# C8T6.net
KiCad netlist of a schematic drawn in Altium Designer
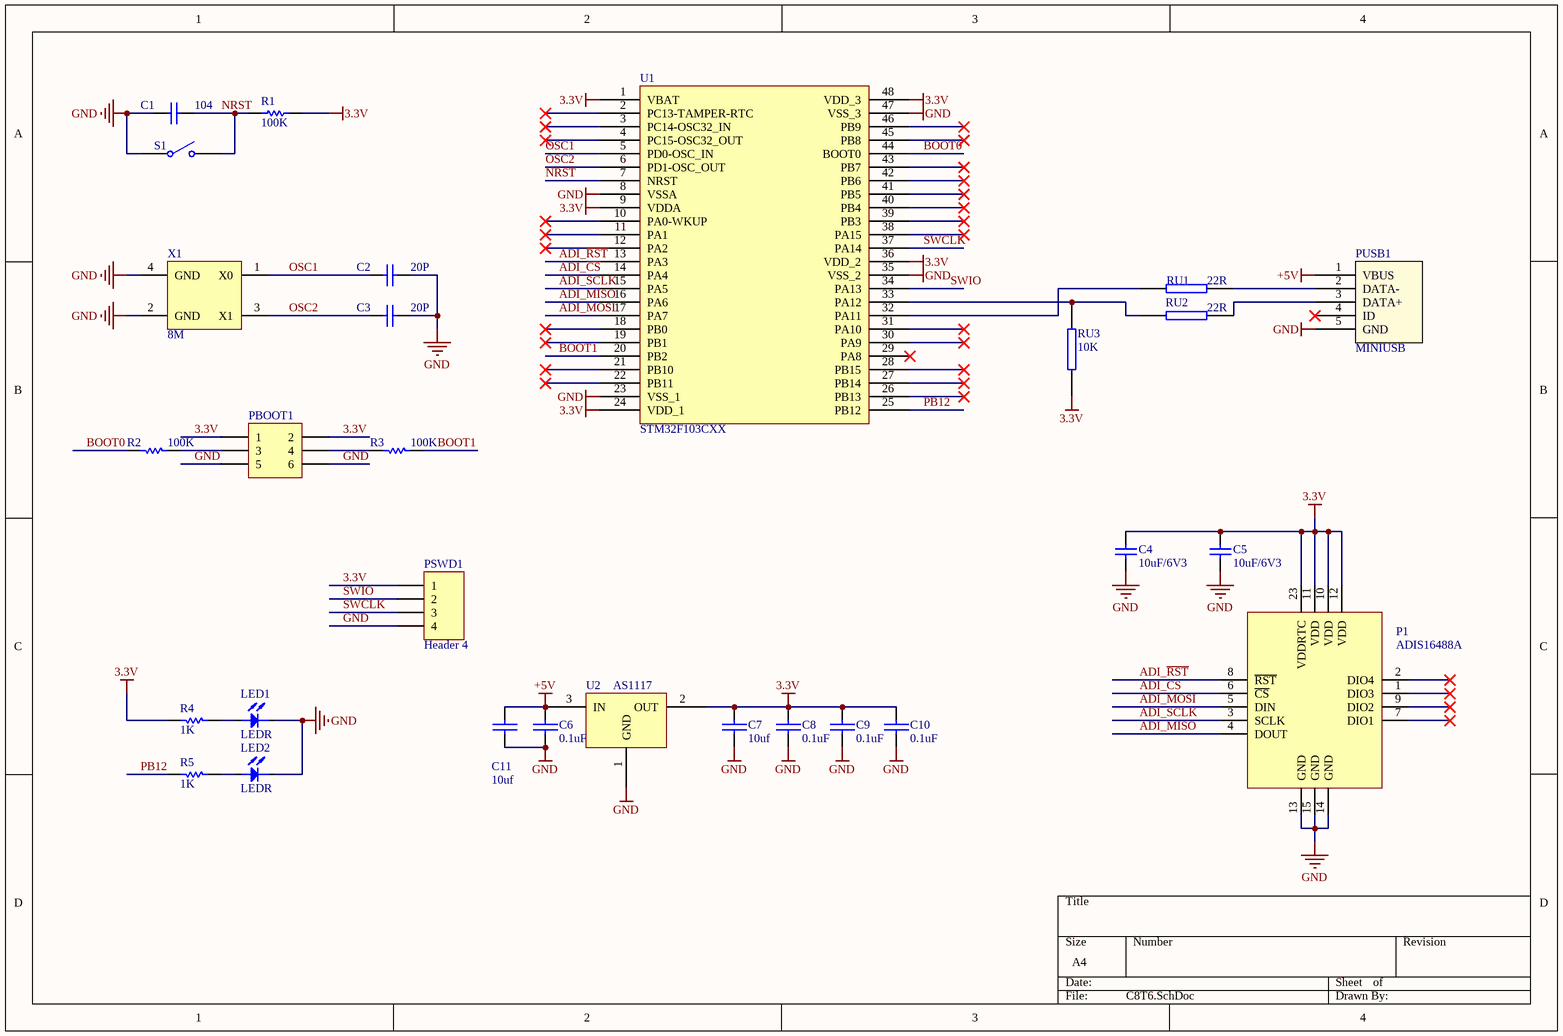
[diagram p0: C8T6.SchDoc]

(export (version "E")
  (design (tool "Eeschema 10.0.6"))
  (components
    (comp (ref "C1")
      (value "104")
      (footprint "0805_C")
      (description "Ceramic Capacitor")
      (fields (field (name "PUBLISHER") "Altium Limited"))
      (libsource (lib "My Devices") (part "Cap Cer"))
    )
    (comp (ref "C2")
      (value "20P")
      (footprint "0805_C")
      (description "Ceramic Capacitor")
      (fields (field (name "PUBLISHER") "Altium Limited"))
      (libsource (lib "My Devices") (part "Cap Cer"))
    )
    (comp (ref "C3")
      (value "20P")
      (footprint "0805_C")
      (description "Ceramic Capacitor")
      (fields (field (name "PUBLISHER") "Altium Limited"))
      (libsource (lib "My Devices") (part "Cap Cer"))
    )
    (comp (ref "C4")
      (value "10uF/6V3")
      (footprint "0805_C")
      (description "Ceramic Capacitor")
      (fields (field (name "PUBLISHER") "Altium Limited"))
      (libsource (lib "My Devices") (part "Cap Cer"))
    )
    (comp (ref "C5")
      (value "10uF/6V3")
      (footprint "0805_C")
      (description "Ceramic Capacitor")
      (fields (field (name "PUBLISHER") "Altium Limited"))
      (libsource (lib "My Devices") (part "Cap Cer"))
    )
    (comp (ref "C6")
      (value "0.1uF")
      (footprint "0805_C")
      (description "Capacitor")
      (libsource (lib "Miscellaneous Devices") (part "CAP"))
    )
    (comp (ref "C7")
      (value "10uf")
      (footprint "0805_C")
      (description "Capacitor")
      (libsource (lib "Miscellaneous Devices") (part "CAP"))
    )
    (comp (ref "C8")
      (value "0.1uF")
      (footprint "0805_C")
      (description "Capacitor")
      (libsource (lib "Miscellaneous Devices") (part "CAP"))
    )
    (comp (ref "C9")
      (value "0.1uF")
      (footprint "0805_C")
      (description "Capacitor")
      (libsource (lib "Miscellaneous Devices") (part "CAP"))
    )
    (comp (ref "C10")
      (value "0.1uF")
      (footprint "0805_C")
      (description "Capacitor")
      (libsource (lib "Miscellaneous Devices") (part "CAP"))
    )
    (comp (ref "C11")
      (value "10uf")
      (footprint "0805_C")
      (description "Capacitor")
      (libsource (lib "Miscellaneous Devices") (part "CAP"))
    )
    (comp (ref "LED1") (value "LEDR") (footprint "0805_R") (libsource (lib "My Devices") (part "LED")))
    (comp (ref "LED2") (value "LEDR") (footprint "0805_R") (libsource (lib "My Devices") (part "LED")))
    (comp (ref "P1")
      (value "ADIS16488A")
      (footprint "ADIS16488A")
      (description "Header, 12-Pin, Dual row")
      (fields (field (name "PUBLISHER") "Altium Limited"))
      (libsource (lib "My Devices") (part "ADIS16488A"))
    )
    (comp (ref "PBOOT1")
      (value "Header 3X2")
      (footprint "HDR2X3")
      (description "Header, 3-Pin, Dual row")
      (fields (field (name "PUBLISHER") "Altium Limited"))
      (libsource (lib "Miscellaneous Connectors") (part "Header 3X2"))
    )
    (comp (ref "PSWD1")
      (value "Header 4")
      (footprint "HDR1X4")
      (description "Header, 4-Pin")
      (fields (field (name "PUBLISHER") "Altium Limited"))
      (libsource (lib "Miscellaneous Connectors") (part "Header 4"))
    )
    (comp (ref "PUSB1") (value "MINIUSB") (footprint "USB_Micro") (libsource (lib "SCH") (part "MINIUSB")))
    (comp (ref "R1")
      (value "100K")
      (footprint "0805_R")
      (description "Resistor")
      (fields (field (name "PUBLISHER") "Altium Limited"))
      (libsource (lib "My Devices") (part "Res"))
    )
    (comp (ref "R2")
      (value "100K")
      (footprint "0805_R")
      (description "Resistor")
      (fields (field (name "PUBLISHER") "Altium Limited"))
      (libsource (lib "My Devices") (part "Res"))
    )
    (comp (ref "R3")
      (value "100K")
      (footprint "0805_R")
      (description "Resistor")
      (fields (field (name "PUBLISHER") "Altium Limited"))
      (libsource (lib "My Devices") (part "Res"))
    )
    (comp (ref "R4")
      (value "1K")
      (footprint "0805_R")
      (description "Resistor")
      (fields (field (name "PUBLISHER") "Altium Limited"))
      (libsource (lib "My Devices") (part "Res"))
    )
    (comp (ref "R5")
      (value "1K")
      (footprint "0805_R")
      (description "Resistor")
      (fields (field (name "PUBLISHER") "Altium Limited"))
      (libsource (lib "My Devices") (part "Res"))
    )
    (comp (ref "RU1")
      (value "22R")
      (footprint "0805_R")
      (libsource (lib "Miscellaneous Devices") (part "RES2"))
    )
    (comp (ref "RU2")
      (value "22R")
      (footprint "0805_R")
      (libsource (lib "Miscellaneous Devices") (part "RES2"))
    )
    (comp (ref "RU3")
      (value "10K")
      (footprint "0805_R")
      (libsource (lib "Miscellaneous Devices") (part "RES2"))
    )
    (comp (ref "S1")
      (value "SW-SPST")
      (footprint "KEY_SMT")
      (description "Single-Pole, Single-Throw Switch")
      (fields (field (name "PUBLISHER") "Altium Limited"))
      (libsource (lib "Miscellaneous Devices") (part "SW-SPST"))
    )
    (comp (ref "U1")
      (value "STM32F103CXX")
      (footprint "LQFP-48_7x7x05P")
      (libsource (lib "STSCH") (part "STM32F103CXX"))
    )
    (comp (ref "U2") (value "AS1117") (footprint "SOT-223") (libsource (lib "SCH") (part "AS1117")))
    (comp (ref "X1")
      (value "8M")
      (footprint "3225-XTAL")
      (description "Crystal")
      (libsource (lib "My Devices") (part "Crystal"))
    )
  )
  (nets
    (net (code "1") (name "+5V") (class "Default")
      (node (ref "C11") (pin "1") (pinfunction "1_1") (pintype "passive"))
      (node (ref "C6") (pin "1") (pinfunction "1_1") (pintype "passive"))
      (node (ref "PUSB1") (pin "1") (pinfunction "VBUS_1") (pintype "passive"))
      (node (ref "U2") (pin "3") (pinfunction "IN_3") (pintype "passive"))
    )
    (net (code "2") (name "/ADI_MISO") (class "Default")
      (node (ref "P1") (pin "4") (pinfunction "DOUT_4") (pintype "passive"))
      (node (ref "U1") (pin "16") (pinfunction "PA6_16") (pintype "passive"))
    )
    (net (code "3") (name "/ADI_MOSI") (class "Default")
      (node (ref "P1") (pin "5") (pinfunction "DIN_5") (pintype "passive"))
      (node (ref "U1") (pin "17") (pinfunction "PA7_17") (pintype "passive"))
    )
    (net (code "4") (name "/ADI_SCLK") (class "Default")
      (node (ref "P1") (pin "3") (pinfunction "SCLK_3") (pintype "passive"))
      (node (ref "U1") (pin "15") (pinfunction "PA5_15") (pintype "passive"))
    )
    (net (code "5") (name "/ADI_~{CS}") (class "Default")
      (node (ref "P1") (pin "6") (pinfunction "~{CS}_6") (pintype "passive"))
      (node (ref "U1") (pin "14") (pinfunction "PA4_14") (pintype "passive"))
    )
    (net (code "6") (name "/ADI_~{RST}") (class "Default")
      (node (ref "P1") (pin "8") (pinfunction "~{RST}_8") (pintype "passive"))
      (node (ref "U1") (pin "13") (pinfunction "PA3_13") (pintype "passive"))
    )
    (net (code "7") (name "/BOOT0") (class "Default")
      (node (ref "R2") (pin "2") (pinfunction "2_2") (pintype "passive"))
      (node (ref "U1") (pin "44") (pinfunction "BOOT0_44") (pintype "passive"))
    )
    (net (code "8") (name "/BOOT1") (class "Default")
      (node (ref "R3") (pin "1") (pinfunction "1_1") (pintype "passive"))
      (node (ref "U1") (pin "20") (pinfunction "PB2_20") (pintype "passive"))
    )
    (net (code "9") (name "/NRST") (class "Default")
      (node (ref "C1") (pin "2") (pinfunction "2_2") (pintype "passive"))
      (node (ref "R1") (pin "1") (pinfunction "1_1") (pintype "passive"))
      (node (ref "S1") (pin "2") (pinfunction "NO_2") (pintype "passive"))
      (node (ref "U1") (pin "7") (pinfunction "NRST_7") (pintype "passive"))
    )
    (net (code "10") (name "/OSC1") (class "Default")
      (node (ref "C2") (pin "1") (pinfunction "1_1") (pintype "passive"))
      (node (ref "U1") (pin "5") (pinfunction "PD0-OSC_IN_5") (pintype "passive"))
      (node (ref "X1") (pin "1") (pinfunction "X0_1") (pintype "passive"))
    )
    (net (code "11") (name "/OSC2") (class "Default")
      (node (ref "C3") (pin "1") (pinfunction "1_1") (pintype "passive"))
      (node (ref "U1") (pin "6") (pinfunction "PD1-OSC_OUT_6") (pintype "passive"))
      (node (ref "X1") (pin "3") (pinfunction "X1_3") (pintype "passive"))
    )
    (net (code "12") (name "/PB12") (class "Default")
      (node (ref "R5") (pin "2") (pinfunction "2_2") (pintype "passive"))
      (node (ref "U1") (pin "25") (pinfunction "PB12_25") (pintype "passive"))
    )
    (net (code "13") (name "/SWCLK") (class "Default")
      (node (ref "PSWD1") (pin "3") (pinfunction "3_3") (pintype "passive"))
      (node (ref "U1") (pin "37") (pinfunction "PA14_37") (pintype "passive"))
    )
    (net (code "14") (name "/SWIO") (class "Default")
      (node (ref "PSWD1") (pin "2") (pinfunction "2_2") (pintype "passive"))
      (node (ref "U1") (pin "34") (pinfunction "PA13_34") (pintype "passive"))
    )
    (net (code "15") (name "3.3V") (class "Default")
      (node (ref "C10") (pin "1") (pinfunction "1_1") (pintype "passive"))
      (node (ref "C4") (pin "2") (pinfunction "2_2") (pintype "passive"))
      (node (ref "C5") (pin "2") (pinfunction "2_2") (pintype "passive"))
      (node (ref "C7") (pin "1") (pinfunction "1_1") (pintype "passive"))
      (node (ref "C8") (pin "1") (pinfunction "1_1") (pintype "passive"))
      (node (ref "C9") (pin "1") (pinfunction "1_1") (pintype "passive"))
      (node (ref "P1") (pin "10") (pinfunction "VDD_10") (pintype "passive"))
      (node (ref "P1") (pin "11") (pinfunction "VDD_11") (pintype "passive"))
      (node (ref "P1") (pin "12") (pinfunction "VDD_12") (pintype "passive"))
      (node (ref "P1") (pin "23") (pinfunction "VDDRTC_23") (pintype "passive"))
      (node (ref "PBOOT1") (pin "1") (pinfunction "1_1") (pintype "passive"))
      (node (ref "PBOOT1") (pin "2") (pinfunction "2_2") (pintype "passive"))
      (node (ref "PSWD1") (pin "1") (pinfunction "1_1") (pintype "passive"))
      (node (ref "R1") (pin "2") (pinfunction "2_2") (pintype "passive"))
      (node (ref "R4") (pin "2") (pinfunction "2_2") (pintype "passive"))
      (node (ref "RU3") (pin "1") (pinfunction "1_1") (pintype "passive"))
      (node (ref "U1") (pin "1") (pinfunction "VBAT_1") (pintype "passive"))
      (node (ref "U1") (pin "24") (pinfunction "VDD_1_24") (pintype "passive"))
      (node (ref "U1") (pin "36") (pinfunction "VDD_2_36") (pintype "passive"))
      (node (ref "U1") (pin "48") (pinfunction "VDD_3_48") (pintype "passive"))
      (node (ref "U1") (pin "9") (pinfunction "VDDA_9") (pintype "passive"))
      (node (ref "U2") (pin "2") (pinfunction "OUT_2") (pintype "passive"))
    )
    (net (code "16") (name "GND") (class "Default")
      (node (ref "C1") (pin "1") (pinfunction "1_1") (pintype "passive"))
      (node (ref "C10") (pin "2") (pinfunction "2_2") (pintype "passive"))
      (node (ref "C11") (pin "2") (pinfunction "2_2") (pintype "passive"))
      (node (ref "C2") (pin "2") (pinfunction "2_2") (pintype "passive"))
      (node (ref "C3") (pin "2") (pinfunction "2_2") (pintype "passive"))
      (node (ref "C4") (pin "1") (pinfunction "1_1") (pintype "passive"))
      (node (ref "C5") (pin "1") (pinfunction "1_1") (pintype "passive"))
      (node (ref "C6") (pin "2") (pinfunction "2_2") (pintype "passive"))
      (node (ref "C7") (pin "2") (pinfunction "2_2") (pintype "passive"))
      (node (ref "C8") (pin "2") (pinfunction "2_2") (pintype "passive"))
      (node (ref "C9") (pin "2") (pinfunction "2_2") (pintype "passive"))
      (node (ref "LED1") (pin "2") (pintype "passive"))
      (node (ref "LED2") (pin "2") (pintype "passive"))
      (node (ref "P1") (pin "13") (pinfunction "GND_13") (pintype "passive"))
      (node (ref "P1") (pin "14") (pinfunction "GND_14") (pintype "passive"))
      (node (ref "P1") (pin "15") (pinfunction "GND_15") (pintype "passive"))
      (node (ref "PBOOT1") (pin "5") (pinfunction "5_5") (pintype "passive"))
      (node (ref "PBOOT1") (pin "6") (pinfunction "6_6") (pintype "passive"))
      (node (ref "PSWD1") (pin "4") (pinfunction "4_4") (pintype "passive"))
      (node (ref "PUSB1") (pin "5") (pinfunction "GND_5") (pintype "passive"))
      (node (ref "S1") (pin "1") (pinfunction "COMMON_1") (pintype "passive"))
      (node (ref "U1") (pin "23") (pinfunction "VSS_1_23") (pintype "passive"))
      (node (ref "U1") (pin "35") (pinfunction "VSS_2_35") (pintype "passive"))
      (node (ref "U1") (pin "47") (pinfunction "VSS_3_47") (pintype "passive"))
      (node (ref "U1") (pin "8") (pinfunction "VSSA_8") (pintype "passive"))
      (node (ref "U2") (pin "1") (pinfunction "GND_1") (pintype "passive"))
      (node (ref "X1") (pin "2") (pinfunction "GND_2") (pintype "passive"))
      (node (ref "X1") (pin "4") (pinfunction "GND_4") (pintype "passive"))
    )
    (net (code "17") (name "Net-(LED1-Pad1)") (class "Default")
      (node (ref "LED1") (pin "1") (pintype "passive"))
      (node (ref "R4") (pin "1") (pinfunction "1_1") (pintype "passive"))
    )
    (net (code "18") (name "Net-(LED2-Pad1)") (class "Default")
      (node (ref "LED2") (pin "1") (pintype "passive"))
      (node (ref "R5") (pin "1") (pinfunction "1_1") (pintype "passive"))
    )
    (net (code "19") (name "Net-(PBOOT1-Pad3)") (class "Default")
      (node (ref "PBOOT1") (pin "3") (pinfunction "3_3") (pintype "passive"))
      (node (ref "R2") (pin "1") (pinfunction "1_1") (pintype "passive"))
    )
    (net (code "20") (name "Net-(PBOOT1-Pad4)") (class "Default")
      (node (ref "PBOOT1") (pin "4") (pinfunction "4_4") (pintype "passive"))
      (node (ref "R3") (pin "2") (pinfunction "2_2") (pintype "passive"))
    )
    (net (code "21") (name "Net-(PUSB1-DATA+)") (class "Default")
      (node (ref "PUSB1") (pin "3") (pinfunction "DATA+_3") (pintype "passive"))
      (node (ref "RU2") (pin "2") (pinfunction "2_2") (pintype "passive"))
    )
    (net (code "22") (name "Net-(PUSB1-DATA-)") (class "Default")
      (node (ref "PUSB1") (pin "2") (pinfunction "DATA-_2") (pintype "passive"))
      (node (ref "RU1") (pin "2") (pinfunction "2_2") (pintype "passive"))
    )
    (net (code "23") (name "Net-(U1-PA11)") (class "Default")
      (node (ref "RU1") (pin "1") (pinfunction "1_1") (pintype "passive"))
      (node (ref "U1") (pin "32") (pinfunction "PA11_32") (pintype "passive"))
    )
    (net (code "24") (name "Net-(U1-PA12)") (class "Default")
      (node (ref "RU2") (pin "1") (pinfunction "1_1") (pintype "passive"))
      (node (ref "RU3") (pin "2") (pinfunction "2_2") (pintype "passive"))
      (node (ref "U1") (pin "33") (pinfunction "PA12_33") (pintype "passive"))
    )
    (net (code "25") (name "unconnected-(P1-DIO1-Pad7)") (class "Default")
      (node (ref "P1") (pin "7") (pinfunction "DIO1_7") (pintype "passive+no_connect"))
    )
    (net (code "26") (name "unconnected-(P1-DIO2-Pad9)") (class "Default")
      (node (ref "P1") (pin "9") (pinfunction "DIO2_9") (pintype "passive+no_connect"))
    )
    (net (code "27") (name "unconnected-(P1-DIO3-Pad1)") (class "Default")
      (node (ref "P1") (pin "1") (pinfunction "DIO3_1") (pintype "passive+no_connect"))
    )
    (net (code "28") (name "unconnected-(P1-DIO4-Pad2)") (class "Default")
      (node (ref "P1") (pin "2") (pinfunction "DIO4_2") (pintype "passive+no_connect"))
    )
    (net (code "29") (name "unconnected-(PUSB1-ID-Pad4)") (class "Default")
      (node (ref "PUSB1") (pin "4") (pinfunction "ID_4") (pintype "passive+no_connect"))
    )
    (net (code "30") (name "unconnected-(U1-PA0-WKUP-Pad10)") (class "Default")
      (node (ref "U1") (pin "10") (pinfunction "PA0-WKUP_10") (pintype "passive+no_connect"))
    )
    (net (code "31") (name "unconnected-(U1-PA1-Pad11)") (class "Default")
      (node (ref "U1") (pin "11") (pinfunction "PA1_11") (pintype "passive+no_connect"))
    )
    (net (code "32") (name "unconnected-(U1-PA2-Pad12)") (class "Default")
      (node (ref "U1") (pin "12") (pinfunction "PA2_12") (pintype "passive+no_connect"))
    )
    (net (code "33") (name "unconnected-(U1-PA8-Pad29)") (class "Default")
      (node (ref "U1") (pin "29") (pinfunction "PA8_29") (pintype "passive+no_connect"))
    )
    (net (code "34") (name "unconnected-(U1-PA9-Pad30)") (class "Default")
      (node (ref "U1") (pin "30") (pinfunction "PA9_30") (pintype "passive+no_connect"))
    )
    (net (code "35") (name "unconnected-(U1-PA10-Pad31)") (class "Default")
      (node (ref "U1") (pin "31") (pinfunction "PA10_31") (pintype "passive+no_connect"))
    )
    (net (code "36") (name "unconnected-(U1-PA15-Pad38)") (class "Default")
      (node (ref "U1") (pin "38") (pinfunction "PA15_38") (pintype "passive+no_connect"))
    )
    (net (code "37") (name "unconnected-(U1-PB0-Pad18)") (class "Default")
      (node (ref "U1") (pin "18") (pinfunction "PB0_18") (pintype "passive+no_connect"))
    )
    (net (code "38") (name "unconnected-(U1-PB1-Pad19)") (class "Default")
      (node (ref "U1") (pin "19") (pinfunction "PB1_19") (pintype "passive+no_connect"))
    )
    (net (code "39") (name "unconnected-(U1-PB3-Pad39)") (class "Default")
      (node (ref "U1") (pin "39") (pinfunction "PB3_39") (pintype "passive+no_connect"))
    )
    (net (code "40") (name "unconnected-(U1-PB4-Pad40)") (class "Default")
      (node (ref "U1") (pin "40") (pinfunction "PB4_40") (pintype "passive+no_connect"))
    )
    (net (code "41") (name "unconnected-(U1-PB5-Pad41)") (class "Default")
      (node (ref "U1") (pin "41") (pinfunction "PB5_41") (pintype "passive+no_connect"))
    )
    (net (code "42") (name "unconnected-(U1-PB6-Pad42)") (class "Default")
      (node (ref "U1") (pin "42") (pinfunction "PB6_42") (pintype "passive+no_connect"))
    )
    (net (code "43") (name "unconnected-(U1-PB7-Pad43)") (class "Default")
      (node (ref "U1") (pin "43") (pinfunction "PB7_43") (pintype "passive+no_connect"))
    )
    (net (code "44") (name "unconnected-(U1-PB8-Pad45)") (class "Default")
      (node (ref "U1") (pin "45") (pinfunction "PB8_45") (pintype "passive+no_connect"))
    )
    (net (code "45") (name "unconnected-(U1-PB9-Pad46)") (class "Default")
      (node (ref "U1") (pin "46") (pinfunction "PB9_46") (pintype "passive+no_connect"))
    )
    (net (code "46") (name "unconnected-(U1-PB10-Pad21)") (class "Default")
      (node (ref "U1") (pin "21") (pinfunction "PB10_21") (pintype "passive+no_connect"))
    )
    (net (code "47") (name "unconnected-(U1-PB11-Pad22)") (class "Default")
      (node (ref "U1") (pin "22") (pinfunction "PB11_22") (pintype "passive+no_connect"))
    )
    (net (code "48") (name "unconnected-(U1-PB13-Pad26)") (class "Default")
      (node (ref "U1") (pin "26") (pinfunction "PB13_26") (pintype "passive+no_connect"))
    )
    (net (code "49") (name "unconnected-(U1-PB14-Pad27)") (class "Default")
      (node (ref "U1") (pin "27") (pinfunction "PB14_27") (pintype "passive+no_connect"))
    )
    (net (code "50") (name "unconnected-(U1-PB15-Pad28)") (class "Default")
      (node (ref "U1") (pin "28") (pinfunction "PB15_28") (pintype "passive+no_connect"))
    )
    (net (code "51") (name "unconnected-(U1-PC13-TAMPER-RTC-Pad2)") (class "Default")
      (node (ref "U1") (pin "2") (pinfunction "PC13-TAMPER-RTC_2") (pintype "passive+no_connect"))
    )
    (net (code "52") (name "unconnected-(U1-PC14-OSC32_IN-Pad3)") (class "Default")
      (node (ref "U1") (pin "3") (pinfunction "PC14-OSC32_IN_3") (pintype "passive+no_connect"))
    )
    (net (code "53") (name "unconnected-(U1-PC15-OSC32_OUT-Pad4)") (class "Default")
      (node (ref "U1") (pin "4") (pinfunction "PC15-OSC32_OUT_4") (pintype "passive+no_connect"))
    )
  )
)
